# extruder_pcb.net
KiCad netlist of a schematic drawn in EAGLE
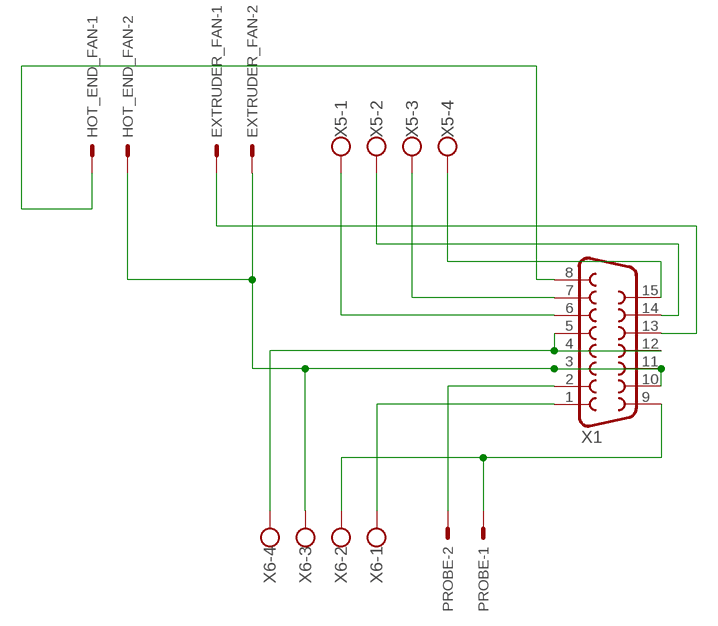
[diagram p0: schematic, sheet 1]

(export (version "E")
  (design (tool "Eeschema 10.0.6"))
  (components
    (comp (ref "EXTRUDER_FAN")
      (value "KK-156-2")
      (footprint "eagle-import:KK-156-2")
      (libsource (lib "eagle-import") (part "KK-156-2"))
    )
    (comp (ref "HOT_END_FAN")
      (value "KK-156-2")
      (footprint "eagle-import:KK-156-2")
      (libsource (lib "eagle-import") (part "KK-156-2"))
    )
    (comp (ref "PROBE")
      (value "KK-156-2")
      (footprint "eagle-import:KK-156-2")
      (libsource (lib "eagle-import") (part "KK-156-2"))
    )
    (comp (ref "X1")
      (value "F15VB")
      (footprint "eagle-import:F15VB")
      (libsource (lib "eagle-import") (part "F15VB"))
    )
    (comp (ref "X5")
      (value "W237-4")
      (footprint "eagle-import:W237-4")
      (libsource (lib "eagle-import") (part "W237-4"))
    )
    (comp (ref "X6")
      (value "W237-4")
      (footprint "eagle-import:W237-4")
      (libsource (lib "eagle-import") (part "W237-4"))
    )
  )
  (nets
    (net (code "1") (name "Net-(EXTRUDER_FANA-S)") (class "Default")
      (node (ref "EXTRUDER_FAN") (pin "1") (pinfunction "S_1") (pintype "passive"))
      (node (ref "X1") (pin "13") (pinfunction "13_13") (pintype "passive"))
    )
    (net (code "2") (name "Net-(EXTRUDER_FANB-S)") (class "Default")
      (node (ref "EXTRUDER_FAN") (pin "2") (pinfunction "S_2") (pintype "passive"))
      (node (ref "HOT_END_FAN") (pin "2") (pinfunction "S_2") (pintype "passive"))
      (node (ref "X1") (pin "10") (pinfunction "10_10") (pintype "passive"))
      (node (ref "X1") (pin "11") (pinfunction "11_11") (pintype "passive"))
      (node (ref "X1") (pin "3") (pinfunction "3_3") (pintype "passive"))
      (node (ref "X6") (pin "3") (pinfunction "KL_3") (pintype "passive"))
    )
    (net (code "3") (name "Net-(HOT_END_FANA-S)") (class "Default")
      (node (ref "HOT_END_FAN") (pin "1") (pinfunction "S_1") (pintype "passive"))
      (node (ref "X1") (pin "8") (pinfunction "8_8") (pintype "passive"))
    )
    (net (code "4") (name "Net-(PROBEA-S)") (class "Default")
      (node (ref "PROBE") (pin "1") (pinfunction "S_1") (pintype "passive"))
      (node (ref "X1") (pin "9") (pinfunction "9_9") (pintype "passive"))
      (node (ref "X6") (pin "2") (pinfunction "KL_2") (pintype "passive"))
    )
    (net (code "5") (name "Net-(PROBEB-S)") (class "Default")
      (node (ref "PROBE") (pin "2") (pinfunction "S_2") (pintype "passive"))
      (node (ref "X1") (pin "2") (pinfunction "2_2") (pintype "passive"))
    )
    (net (code "6") (name "Net-(X5A-KL)") (class "Default")
      (node (ref "X1") (pin "6") (pinfunction "6_6") (pintype "passive"))
      (node (ref "X5") (pin "1") (pinfunction "KL_1") (pintype "passive"))
    )
    (net (code "7") (name "Net-(X5B-KL)") (class "Default")
      (node (ref "X1") (pin "14") (pinfunction "14_14") (pintype "passive"))
      (node (ref "X5") (pin "2") (pinfunction "KL_2") (pintype "passive"))
    )
    (net (code "8") (name "Net-(X5C-KL)") (class "Default")
      (node (ref "X1") (pin "7") (pinfunction "7_7") (pintype "passive"))
      (node (ref "X5") (pin "3") (pinfunction "KL_3") (pintype "passive"))
    )
    (net (code "9") (name "Net-(X5D-KL)") (class "Default")
      (node (ref "X1") (pin "15") (pinfunction "15_15") (pintype "passive"))
      (node (ref "X5") (pin "4") (pinfunction "KL_4") (pintype "passive"))
    )
    (net (code "10") (name "Net-(X6A-KL)") (class "Default")
      (node (ref "X1") (pin "1") (pinfunction "1_1") (pintype "passive"))
      (node (ref "X6") (pin "1") (pinfunction "KL_1") (pintype "passive"))
    )
    (net (code "11") (name "Net-(X6D-KL)") (class "Default")
      (node (ref "X1") (pin "12") (pinfunction "12_12") (pintype "passive"))
      (node (ref "X1") (pin "4") (pinfunction "4_4") (pintype "passive"))
      (node (ref "X1") (pin "5") (pinfunction "5_5") (pintype "passive"))
      (node (ref "X6") (pin "4") (pinfunction "KL_4") (pintype "passive"))
    )
  )
)
